# u16_zxbus_rev_a.net
KiCad netlist of a schematic drawn in EAGLE
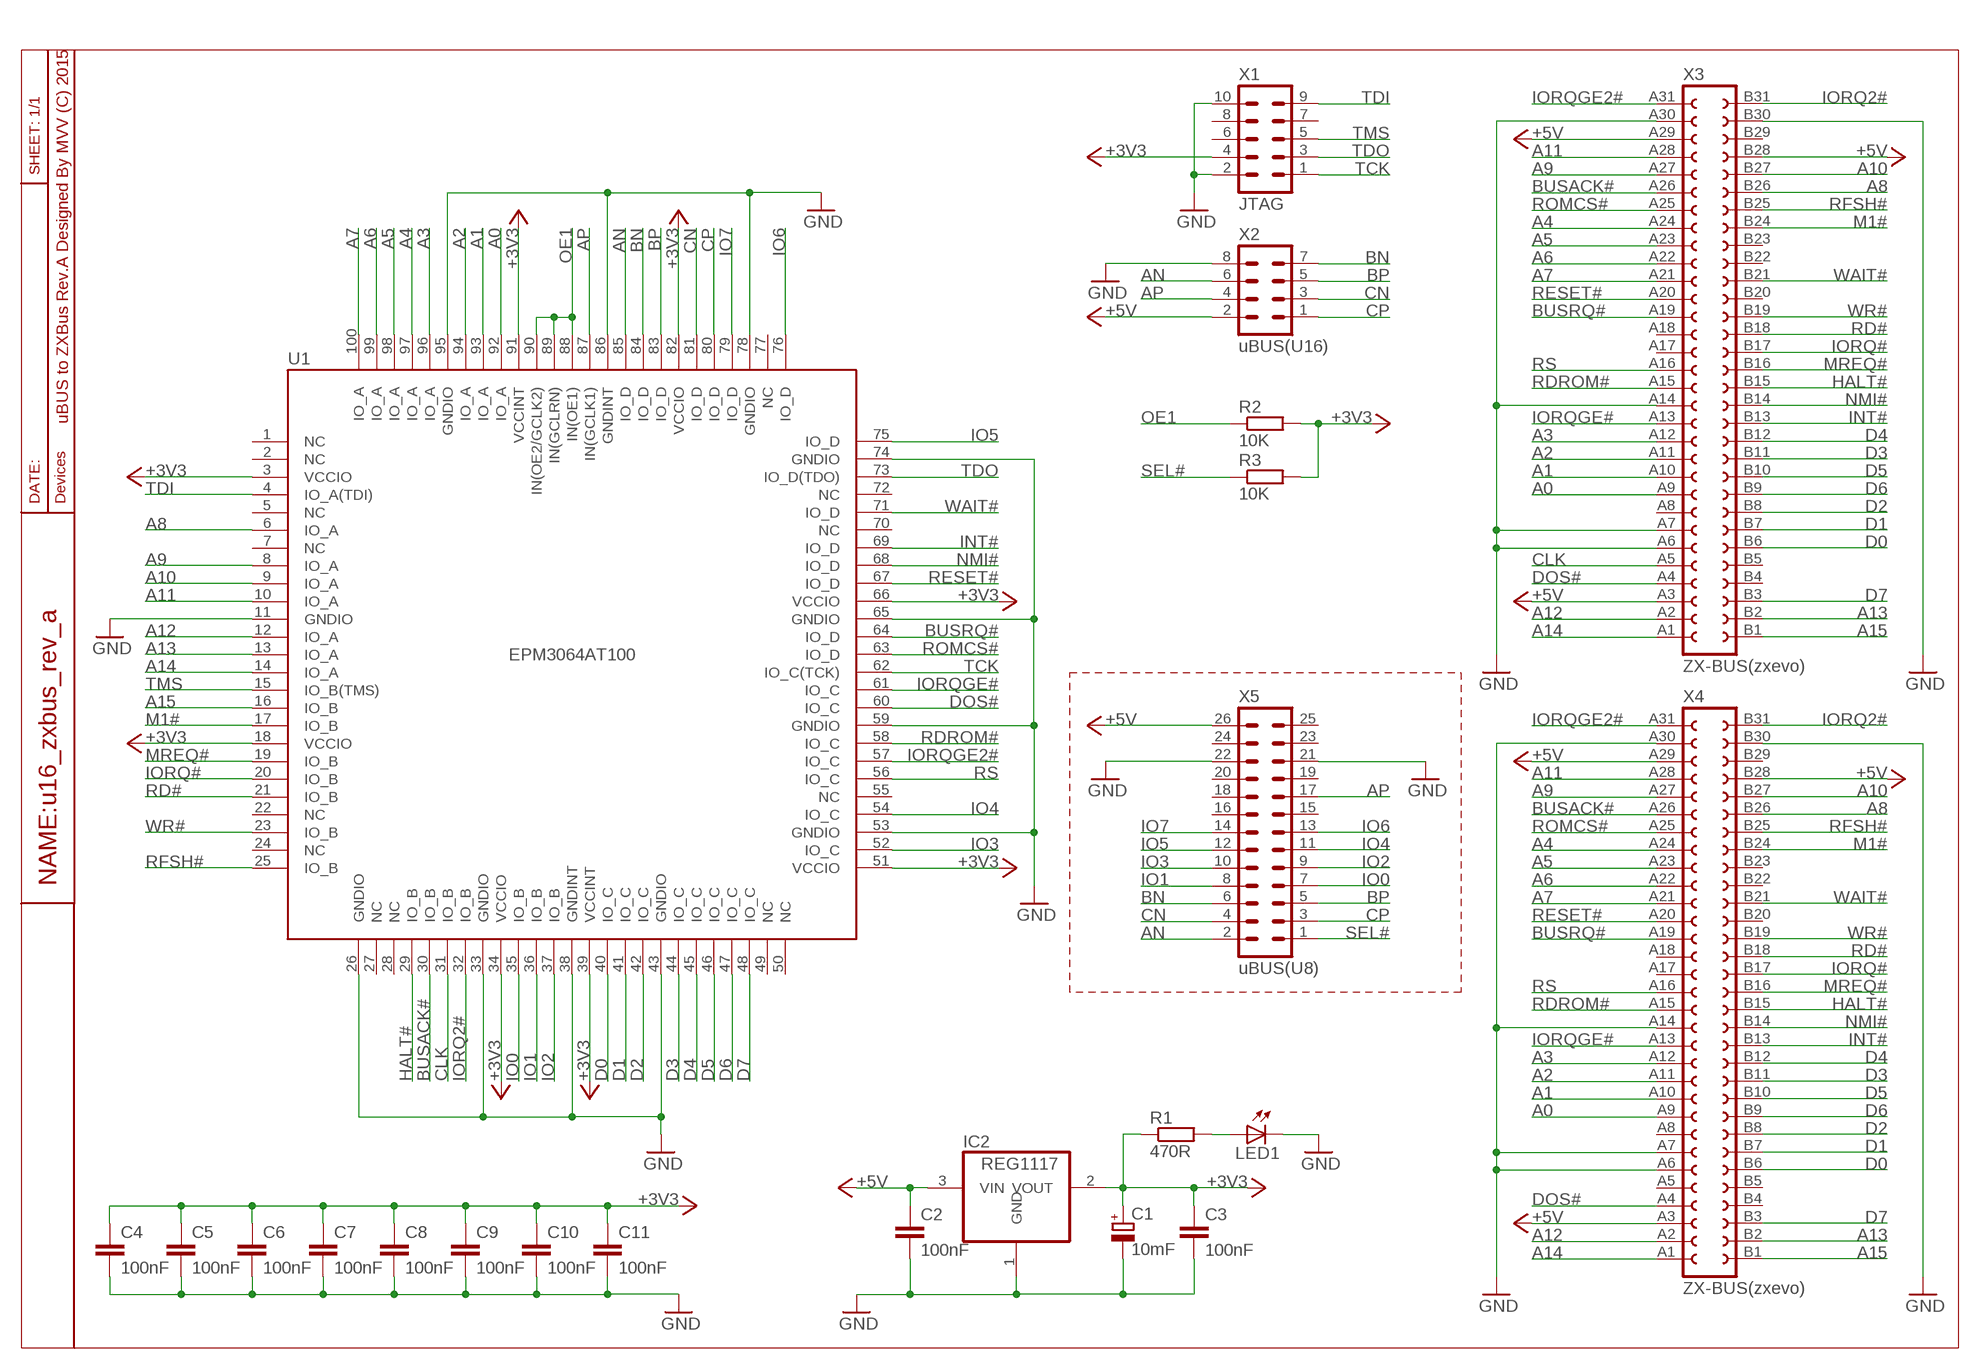
[diagram p0: schematic, sheet 1]

(export (version "E")
  (design (tool "Eeschema 10.0.6"))
  (components
    (comp (ref "C1")
      (value "10mF")
      (footprint "eagle-import:CT6032")
      (libsource (lib "eagle-import") (part "CPOL-EUCT6032"))
    )
    (comp (ref "C2")
      (value "100nF")
      (footprint "eagle-import:C0805")
      (libsource (lib "eagle-import") (part "C-EUC0805"))
    )
    (comp (ref "C3")
      (value "100nF")
      (footprint "eagle-import:C0805")
      (libsource (lib "eagle-import") (part "C-EUC0805"))
    )
    (comp (ref "C4")
      (value "100nF")
      (footprint "eagle-import:C0805")
      (libsource (lib "eagle-import") (part "C-EUC0805"))
    )
    (comp (ref "C5")
      (value "100nF")
      (footprint "eagle-import:C0805")
      (libsource (lib "eagle-import") (part "C-EUC0805"))
    )
    (comp (ref "C6")
      (value "100nF")
      (footprint "eagle-import:C0805")
      (libsource (lib "eagle-import") (part "C-EUC0805"))
    )
    (comp (ref "C7")
      (value "100nF")
      (footprint "eagle-import:C0805")
      (libsource (lib "eagle-import") (part "C-EUC0805"))
    )
    (comp (ref "C8")
      (value "100nF")
      (footprint "eagle-import:C0805")
      (libsource (lib "eagle-import") (part "C-EUC0805"))
    )
    (comp (ref "C9")
      (value "100nF")
      (footprint "eagle-import:C0805")
      (libsource (lib "eagle-import") (part "C-EUC0805"))
    )
    (comp (ref "C10")
      (value "100nF")
      (footprint "eagle-import:C0805")
      (libsource (lib "eagle-import") (part "C-EUC0805"))
    )
    (comp (ref "C11")
      (value "100nF")
      (footprint "eagle-import:C0805")
      (libsource (lib "eagle-import") (part "C-EUC0805"))
    )
    (comp (ref "IC2")
      (value "REG1117")
      (footprint "eagle-import:SOT223")
      (libsource (lib "eagle-import") (part "REG1117"))
    )
    (comp (ref "LED1")
      (value "LEDCHIPLED_0805")
      (footprint "eagle-import:CHIPLED_0805")
      (libsource (lib "eagle-import") (part "LEDCHIPLED_0805"))
    )
    (comp (ref "R1")
      (value "470R")
      (footprint "eagle-import:R0805")
      (libsource (lib "eagle-import") (part "R-EU_R0805"))
    )
    (comp (ref "R2")
      (value "10K")
      (footprint "eagle-import:R0805")
      (libsource (lib "eagle-import") (part "R-EU_R0805"))
    )
    (comp (ref "R3")
      (value "10K")
      (footprint "eagle-import:R0805")
      (libsource (lib "eagle-import") (part "R-EU_R0805"))
    )
    (comp (ref "U1")
      (value "EPM3064AT100")
      (footprint "eagle-import:TQFP100")
      (libsource (lib "eagle-import") (part "EPM3064AT100"))
    )
    (comp (ref "X1")
      (value "JTAG")
      (footprint "eagle-import:ML10")
      (libsource (lib "eagle-import") (part "ML10"))
    )
    (comp (ref "X2")
      (value "uBUS(U16)")
      (footprint "eagle-import:MA04-2")
      (libsource (lib "eagle-import") (part "MA04-2"))
    )
    (comp (ref "X3")
      (value "ZX-BUS(zxevo)")
      (footprint "eagle-import:FE31-2")
      (libsource (lib "eagle-import") (part "FE31-2"))
    )
    (comp (ref "X4")
      (value "ZX-BUS(zxevo)")
      (footprint "eagle-import:ESO3101")
      (libsource (lib "eagle-import") (part "ESO3101"))
    )
    (comp (ref "X5")
      (value "uBUS(U8)")
      (footprint "eagle-import:ML26")
      (libsource (lib "eagle-import") (part "ML26"))
    )
  )
  (nets
    (net (code "1") (name "+3V3") (class "Default")
      (node (ref "C1") (pin "+") (pinfunction "+_+") (pintype "passive"))
      (node (ref "C10") (pin "1") (pinfunction "1_1") (pintype "passive"))
      (node (ref "C11") (pin "1") (pinfunction "1_1") (pintype "passive"))
      (node (ref "C3") (pin "1") (pinfunction "1_1") (pintype "passive"))
      (node (ref "C4") (pin "1") (pinfunction "1_1") (pintype "passive"))
      (node (ref "C5") (pin "1") (pinfunction "1_1") (pintype "passive"))
      (node (ref "C6") (pin "1") (pinfunction "1_1") (pintype "passive"))
      (node (ref "C7") (pin "1") (pinfunction "1_1") (pintype "passive"))
      (node (ref "C8") (pin "1") (pinfunction "1_1") (pintype "passive"))
      (node (ref "C9") (pin "1") (pinfunction "1_1") (pintype "passive"))
      (node (ref "IC2") (pin "2") (pinfunction "VOUT_2") (pintype "output"))
      (node (ref "R1") (pin "1") (pinfunction "1_1") (pintype "passive"))
      (node (ref "R2") (pin "2") (pinfunction "2_2") (pintype "passive"))
      (node (ref "R3") (pin "2") (pinfunction "2_2") (pintype "passive"))
      (node (ref "U1") (pin "18") (pinfunction "VCCIO_18") (pintype "power_in"))
      (node (ref "U1") (pin "3") (pinfunction "VCCIO_3") (pintype "power_in"))
      (node (ref "U1") (pin "34") (pinfunction "VCCIO_34") (pintype "power_in"))
      (node (ref "U1") (pin "39") (pinfunction "VCCINT_39") (pintype "power_in"))
      (node (ref "U1") (pin "51") (pinfunction "VCCIO_51") (pintype "power_in"))
      (node (ref "U1") (pin "66") (pinfunction "VCCIO_66") (pintype "power_in"))
      (node (ref "U1") (pin "82") (pinfunction "VCCIO_82") (pintype "power_in"))
      (node (ref "U1") (pin "91") (pinfunction "VCCINT_91") (pintype "power_in"))
      (node (ref "X1") (pin "4") (pinfunction "4_4") (pintype "passive"))
    )
    (net (code "2") (name "+5V") (class "Default")
      (node (ref "C2") (pin "1") (pinfunction "1_1") (pintype "passive"))
      (node (ref "IC2") (pin "3") (pinfunction "VIN_3") (pintype "input"))
      (node (ref "X2") (pin "2") (pinfunction "2_2") (pintype "passive"))
      (node (ref "X3") (pin "A29") (pinfunction "A29_A29") (pintype "passive"))
      (node (ref "X3") (pin "A3") (pinfunction "A3_A3") (pintype "passive"))
      (node (ref "X3") (pin "B28") (pinfunction "B28_B28") (pintype "passive"))
      (node (ref "X4") (pin "A29") (pinfunction "A29_A29") (pintype "passive"))
      (node (ref "X4") (pin "A3") (pinfunction "A3_A3") (pintype "passive"))
      (node (ref "X4") (pin "B28") (pinfunction "B28_B28") (pintype "passive"))
      (node (ref "X5") (pin "26") (pinfunction "26_26") (pintype "passive"))
    )
    (net (code "3") (name "/A0") (class "Default")
      (node (ref "U1") (pin "92") (pinfunction "IO_A_92") (pintype "bidirectional"))
      (node (ref "X3") (pin "A9") (pinfunction "A9_A9") (pintype "passive"))
      (node (ref "X4") (pin "A9") (pinfunction "A9_A9") (pintype "passive"))
    )
    (net (code "4") (name "/A1") (class "Default")
      (node (ref "U1") (pin "93") (pinfunction "IO_A_93") (pintype "bidirectional"))
      (node (ref "X3") (pin "A10") (pinfunction "A10_A10") (pintype "passive"))
      (node (ref "X4") (pin "A10") (pinfunction "A10_A10") (pintype "passive"))
    )
    (net (code "5") (name "/A2") (class "Default")
      (node (ref "U1") (pin "94") (pinfunction "IO_A_94") (pintype "bidirectional"))
      (node (ref "X3") (pin "A11") (pinfunction "A11_A11") (pintype "passive"))
      (node (ref "X4") (pin "A11") (pinfunction "A11_A11") (pintype "passive"))
    )
    (net (code "6") (name "/A3") (class "Default")
      (node (ref "U1") (pin "96") (pinfunction "IO_A_96") (pintype "bidirectional"))
      (node (ref "X3") (pin "A12") (pinfunction "A12_A12") (pintype "passive"))
      (node (ref "X4") (pin "A12") (pinfunction "A12_A12") (pintype "passive"))
    )
    (net (code "7") (name "/A4") (class "Default")
      (node (ref "U1") (pin "97") (pinfunction "IO_A_97") (pintype "bidirectional"))
      (node (ref "X3") (pin "A24") (pinfunction "A24_A24") (pintype "passive"))
      (node (ref "X4") (pin "A24") (pinfunction "A24_A24") (pintype "passive"))
    )
    (net (code "8") (name "/A5") (class "Default")
      (node (ref "U1") (pin "98") (pinfunction "IO_A_98") (pintype "bidirectional"))
      (node (ref "X3") (pin "A23") (pinfunction "A23_A23") (pintype "passive"))
      (node (ref "X4") (pin "A23") (pinfunction "A23_A23") (pintype "passive"))
    )
    (net (code "9") (name "/A6") (class "Default")
      (node (ref "U1") (pin "99") (pinfunction "IO_A_99") (pintype "bidirectional"))
      (node (ref "X3") (pin "A22") (pinfunction "A22_A22") (pintype "passive"))
      (node (ref "X4") (pin "A22") (pinfunction "A22_A22") (pintype "passive"))
    )
    (net (code "10") (name "/A7") (class "Default")
      (node (ref "U1") (pin "100") (pinfunction "IO_A_100") (pintype "bidirectional"))
      (node (ref "X3") (pin "A21") (pinfunction "A21_A21") (pintype "passive"))
      (node (ref "X4") (pin "A21") (pinfunction "A21_A21") (pintype "passive"))
    )
    (net (code "11") (name "/A8") (class "Default")
      (node (ref "U1") (pin "6") (pinfunction "IO_A_6") (pintype "bidirectional"))
      (node (ref "X3") (pin "B26") (pinfunction "B26_B26") (pintype "passive"))
      (node (ref "X4") (pin "B26") (pinfunction "B26_B26") (pintype "passive"))
    )
    (net (code "12") (name "/A9") (class "Default")
      (node (ref "U1") (pin "8") (pinfunction "IO_A_8") (pintype "bidirectional"))
      (node (ref "X3") (pin "A27") (pinfunction "A27_A27") (pintype "passive"))
      (node (ref "X4") (pin "A27") (pinfunction "A27_A27") (pintype "passive"))
    )
    (net (code "13") (name "/A10") (class "Default")
      (node (ref "U1") (pin "9") (pinfunction "IO_A_9") (pintype "bidirectional"))
      (node (ref "X3") (pin "B27") (pinfunction "B27_B27") (pintype "passive"))
      (node (ref "X4") (pin "B27") (pinfunction "B27_B27") (pintype "passive"))
    )
    (net (code "14") (name "/A11") (class "Default")
      (node (ref "U1") (pin "10") (pinfunction "IO_A_10") (pintype "bidirectional"))
      (node (ref "X3") (pin "A28") (pinfunction "A28_A28") (pintype "passive"))
      (node (ref "X4") (pin "A28") (pinfunction "A28_A28") (pintype "passive"))
    )
    (net (code "15") (name "/A12") (class "Default")
      (node (ref "U1") (pin "12") (pinfunction "IO_A_12") (pintype "bidirectional"))
      (node (ref "X3") (pin "A2") (pinfunction "A2_A2") (pintype "passive"))
      (node (ref "X4") (pin "A2") (pinfunction "A2_A2") (pintype "passive"))
    )
    (net (code "16") (name "/A13") (class "Default")
      (node (ref "U1") (pin "13") (pinfunction "IO_A_13") (pintype "bidirectional"))
      (node (ref "X3") (pin "B2") (pinfunction "B2_B2") (pintype "passive"))
      (node (ref "X4") (pin "B2") (pinfunction "B2_B2") (pintype "passive"))
    )
    (net (code "17") (name "/A14") (class "Default")
      (node (ref "U1") (pin "14") (pinfunction "IO_A_14") (pintype "bidirectional"))
      (node (ref "X3") (pin "A1") (pinfunction "A1_A1") (pintype "passive"))
      (node (ref "X4") (pin "A1") (pinfunction "A1_A1") (pintype "passive"))
    )
    (net (code "18") (name "/A15") (class "Default")
      (node (ref "U1") (pin "16") (pinfunction "IO_B_16") (pintype "bidirectional"))
      (node (ref "X3") (pin "B1") (pinfunction "B1_B1") (pintype "passive"))
      (node (ref "X4") (pin "B1") (pinfunction "B1_B1") (pintype "passive"))
    )
    (net (code "19") (name "/AN") (class "Default")
      (node (ref "U1") (pin "85") (pinfunction "IO_D_85") (pintype "bidirectional"))
      (node (ref "X2") (pin "6") (pinfunction "6_6") (pintype "passive"))
      (node (ref "X5") (pin "2") (pinfunction "2_2") (pintype "passive"))
    )
    (net (code "20") (name "/AP") (class "Default")
      (node (ref "U1") (pin "87") (pinfunction "IN(GCLK1)_87") (pintype "input"))
      (node (ref "X2") (pin "4") (pinfunction "4_4") (pintype "passive"))
      (node (ref "X5") (pin "17") (pinfunction "17_17") (pintype "passive"))
    )
    (net (code "21") (name "/BN") (class "Default")
      (node (ref "U1") (pin "84") (pinfunction "IO_D_84") (pintype "bidirectional"))
      (node (ref "X2") (pin "7") (pinfunction "7_7") (pintype "passive"))
      (node (ref "X5") (pin "6") (pinfunction "6_6") (pintype "passive"))
    )
    (net (code "22") (name "/BP") (class "Default")
      (node (ref "U1") (pin "83") (pinfunction "IO_D_83") (pintype "bidirectional"))
      (node (ref "X2") (pin "5") (pinfunction "5_5") (pintype "passive"))
      (node (ref "X5") (pin "5") (pinfunction "5_5") (pintype "passive"))
    )
    (net (code "23") (name "/BUSACK#") (class "Default")
      (node (ref "U1") (pin "30") (pinfunction "IO_B_30") (pintype "bidirectional"))
      (node (ref "X3") (pin "A26") (pinfunction "A26_A26") (pintype "passive"))
      (node (ref "X4") (pin "A26") (pinfunction "A26_A26") (pintype "passive"))
    )
    (net (code "24") (name "/BUSRQ#") (class "Default")
      (node (ref "U1") (pin "64") (pinfunction "IO_D_64") (pintype "bidirectional"))
      (node (ref "X3") (pin "A19") (pinfunction "A19_A19") (pintype "passive"))
      (node (ref "X4") (pin "A19") (pinfunction "A19_A19") (pintype "passive"))
    )
    (net (code "25") (name "/CLK") (class "Default")
      (node (ref "U1") (pin "31") (pinfunction "IO_B_31") (pintype "bidirectional"))
      (node (ref "X3") (pin "A5") (pinfunction "A5_A5") (pintype "passive"))
    )
    (net (code "26") (name "/CN") (class "Default")
      (node (ref "U1") (pin "81") (pinfunction "IO_D_81") (pintype "bidirectional"))
      (node (ref "X2") (pin "3") (pinfunction "3_3") (pintype "passive"))
      (node (ref "X5") (pin "4") (pinfunction "4_4") (pintype "passive"))
    )
    (net (code "27") (name "/CP") (class "Default")
      (node (ref "U1") (pin "80") (pinfunction "IO_D_80") (pintype "bidirectional"))
      (node (ref "X2") (pin "1") (pinfunction "1_1") (pintype "passive"))
      (node (ref "X5") (pin "3") (pinfunction "3_3") (pintype "passive"))
    )
    (net (code "28") (name "/D0") (class "Default")
      (node (ref "U1") (pin "40") (pinfunction "IO_C_40") (pintype "bidirectional"))
      (node (ref "X3") (pin "B6") (pinfunction "B6_B6") (pintype "passive"))
      (node (ref "X4") (pin "B6") (pinfunction "B6_B6") (pintype "passive"))
    )
    (net (code "29") (name "/D1") (class "Default")
      (node (ref "U1") (pin "41") (pinfunction "IO_C_41") (pintype "bidirectional"))
      (node (ref "X3") (pin "B7") (pinfunction "B7_B7") (pintype "passive"))
      (node (ref "X4") (pin "B7") (pinfunction "B7_B7") (pintype "passive"))
    )
    (net (code "30") (name "/D2") (class "Default")
      (node (ref "U1") (pin "42") (pinfunction "IO_C_42") (pintype "bidirectional"))
      (node (ref "X3") (pin "B8") (pinfunction "B8_B8") (pintype "passive"))
      (node (ref "X4") (pin "B8") (pinfunction "B8_B8") (pintype "passive"))
    )
    (net (code "31") (name "/D3") (class "Default")
      (node (ref "U1") (pin "44") (pinfunction "IO_C_44") (pintype "bidirectional"))
      (node (ref "X3") (pin "B11") (pinfunction "B11_B11") (pintype "passive"))
      (node (ref "X4") (pin "B11") (pinfunction "B11_B11") (pintype "passive"))
    )
    (net (code "32") (name "/D4") (class "Default")
      (node (ref "U1") (pin "45") (pinfunction "IO_C_45") (pintype "bidirectional"))
      (node (ref "X3") (pin "B12") (pinfunction "B12_B12") (pintype "passive"))
      (node (ref "X4") (pin "B12") (pinfunction "B12_B12") (pintype "passive"))
    )
    (net (code "33") (name "/D5") (class "Default")
      (node (ref "U1") (pin "46") (pinfunction "IO_C_46") (pintype "bidirectional"))
      (node (ref "X3") (pin "B10") (pinfunction "B10_B10") (pintype "passive"))
      (node (ref "X4") (pin "B10") (pinfunction "B10_B10") (pintype "passive"))
    )
    (net (code "34") (name "/D6") (class "Default")
      (node (ref "U1") (pin "47") (pinfunction "IO_C_47") (pintype "bidirectional"))
      (node (ref "X3") (pin "B9") (pinfunction "B9_B9") (pintype "passive"))
      (node (ref "X4") (pin "B9") (pinfunction "B9_B9") (pintype "passive"))
    )
    (net (code "35") (name "/D7") (class "Default")
      (node (ref "U1") (pin "48") (pinfunction "IO_C_48") (pintype "bidirectional"))
      (node (ref "X3") (pin "B3") (pinfunction "B3_B3") (pintype "passive"))
      (node (ref "X4") (pin "B3") (pinfunction "B3_B3") (pintype "passive"))
    )
    (net (code "36") (name "/DOS#") (class "Default")
      (node (ref "U1") (pin "60") (pinfunction "IO_C_60") (pintype "bidirectional"))
      (node (ref "X3") (pin "A4") (pinfunction "A4_A4") (pintype "passive"))
      (node (ref "X4") (pin "A4") (pinfunction "A4_A4") (pintype "passive"))
    )
    (net (code "37") (name "/HALT#") (class "Default")
      (node (ref "U1") (pin "29") (pinfunction "IO_B_29") (pintype "bidirectional"))
      (node (ref "X3") (pin "B15") (pinfunction "B15_B15") (pintype "passive"))
      (node (ref "X4") (pin "B15") (pinfunction "B15_B15") (pintype "passive"))
    )
    (net (code "38") (name "/INT#") (class "Default")
      (node (ref "U1") (pin "69") (pinfunction "IO_D_69") (pintype "bidirectional"))
      (node (ref "X3") (pin "B13") (pinfunction "B13_B13") (pintype "passive"))
      (node (ref "X4") (pin "B13") (pinfunction "B13_B13") (pintype "passive"))
    )
    (net (code "39") (name "/IO0") (class "Default")
      (node (ref "U1") (pin "35") (pinfunction "IO_B_35") (pintype "bidirectional"))
      (node (ref "X5") (pin "7") (pinfunction "7_7") (pintype "passive"))
    )
    (net (code "40") (name "/IO1") (class "Default")
      (node (ref "U1") (pin "36") (pinfunction "IO_B_36") (pintype "bidirectional"))
      (node (ref "X5") (pin "8") (pinfunction "8_8") (pintype "passive"))
    )
    (net (code "41") (name "/IO2") (class "Default")
      (node (ref "U1") (pin "37") (pinfunction "IO_B_37") (pintype "bidirectional"))
      (node (ref "X5") (pin "9") (pinfunction "9_9") (pintype "passive"))
    )
    (net (code "42") (name "/IO3") (class "Default")
      (node (ref "U1") (pin "52") (pinfunction "IO_C_52") (pintype "bidirectional"))
      (node (ref "X5") (pin "10") (pinfunction "10_10") (pintype "passive"))
    )
    (net (code "43") (name "/IO4") (class "Default")
      (node (ref "U1") (pin "54") (pinfunction "IO_C_54") (pintype "bidirectional"))
      (node (ref "X5") (pin "11") (pinfunction "11_11") (pintype "passive"))
    )
    (net (code "44") (name "/IO5") (class "Default")
      (node (ref "U1") (pin "75") (pinfunction "IO_D_75") (pintype "bidirectional"))
      (node (ref "X5") (pin "12") (pinfunction "12_12") (pintype "passive"))
    )
    (net (code "45") (name "/IO6") (class "Default")
      (node (ref "U1") (pin "76") (pinfunction "IO_D_76") (pintype "bidirectional"))
      (node (ref "X5") (pin "13") (pinfunction "13_13") (pintype "passive"))
    )
    (net (code "46") (name "/IO7") (class "Default")
      (node (ref "U1") (pin "79") (pinfunction "IO_D_79") (pintype "bidirectional"))
      (node (ref "X5") (pin "14") (pinfunction "14_14") (pintype "passive"))
    )
    (net (code "47") (name "/IORQ#") (class "Default")
      (node (ref "U1") (pin "20") (pinfunction "IO_B_20") (pintype "bidirectional"))
      (node (ref "X3") (pin "B17") (pinfunction "B17_B17") (pintype "passive"))
      (node (ref "X4") (pin "B17") (pinfunction "B17_B17") (pintype "passive"))
    )
    (net (code "48") (name "/IORQ2#") (class "Default")
      (node (ref "U1") (pin "32") (pinfunction "IO_B_32") (pintype "bidirectional"))
      (node (ref "X3") (pin "B31") (pinfunction "B31_B31") (pintype "passive"))
      (node (ref "X4") (pin "B31") (pinfunction "B31_B31") (pintype "passive"))
    )
    (net (code "49") (name "/IORQGE#") (class "Default")
      (node (ref "U1") (pin "61") (pinfunction "IO_C_61") (pintype "bidirectional"))
      (node (ref "X3") (pin "A13") (pinfunction "A13_A13") (pintype "passive"))
      (node (ref "X4") (pin "A13") (pinfunction "A13_A13") (pintype "passive"))
    )
    (net (code "50") (name "/IORQGE2#") (class "Default")
      (node (ref "U1") (pin "57") (pinfunction "IO_C_57") (pintype "bidirectional"))
      (node (ref "X3") (pin "A31") (pinfunction "A31_A31") (pintype "passive"))
      (node (ref "X4") (pin "A31") (pinfunction "A31_A31") (pintype "passive"))
    )
    (net (code "51") (name "/M1#") (class "Default")
      (node (ref "U1") (pin "17") (pinfunction "IO_B_17") (pintype "bidirectional"))
      (node (ref "X3") (pin "B24") (pinfunction "B24_B24") (pintype "passive"))
      (node (ref "X4") (pin "B24") (pinfunction "B24_B24") (pintype "passive"))
    )
    (net (code "52") (name "/MREQ#") (class "Default")
      (node (ref "U1") (pin "19") (pinfunction "IO_B_19") (pintype "bidirectional"))
      (node (ref "X3") (pin "B16") (pinfunction "B16_B16") (pintype "passive"))
      (node (ref "X4") (pin "B16") (pinfunction "B16_B16") (pintype "passive"))
    )
    (net (code "53") (name "/NMI#") (class "Default")
      (node (ref "U1") (pin "68") (pinfunction "IO_D_68") (pintype "bidirectional"))
      (node (ref "X3") (pin "B14") (pinfunction "B14_B14") (pintype "passive"))
      (node (ref "X4") (pin "B14") (pinfunction "B14_B14") (pintype "passive"))
    )
    (net (code "54") (name "/OE1") (class "Default")
      (node (ref "R2") (pin "1") (pinfunction "1_1") (pintype "passive"))
      (node (ref "U1") (pin "88") (pinfunction "IN(OE1)_88") (pintype "input"))
      (node (ref "U1") (pin "89") (pinfunction "IN(GCLRN)_89") (pintype "input"))
      (node (ref "U1") (pin "90") (pinfunction "IN(OE2/GCLK2)_90") (pintype "input"))
    )
    (net (code "55") (name "/RD#") (class "Default")
      (node (ref "U1") (pin "21") (pinfunction "IO_B_21") (pintype "bidirectional"))
      (node (ref "X3") (pin "B18") (pinfunction "B18_B18") (pintype "passive"))
      (node (ref "X4") (pin "B18") (pinfunction "B18_B18") (pintype "passive"))
    )
    (net (code "56") (name "/RDROM#") (class "Default")
      (node (ref "U1") (pin "58") (pinfunction "IO_C_58") (pintype "bidirectional"))
      (node (ref "X3") (pin "A15") (pinfunction "A15_A15") (pintype "passive"))
      (node (ref "X4") (pin "A15") (pinfunction "A15_A15") (pintype "passive"))
    )
    (net (code "57") (name "/RESET#") (class "Default")
      (node (ref "U1") (pin "67") (pinfunction "IO_D_67") (pintype "bidirectional"))
      (node (ref "X3") (pin "A20") (pinfunction "A20_A20") (pintype "passive"))
      (node (ref "X4") (pin "A20") (pinfunction "A20_A20") (pintype "passive"))
    )
    (net (code "58") (name "/RFSH#") (class "Default")
      (node (ref "U1") (pin "25") (pinfunction "IO_B_25") (pintype "bidirectional"))
      (node (ref "X3") (pin "B25") (pinfunction "B25_B25") (pintype "passive"))
      (node (ref "X4") (pin "B25") (pinfunction "B25_B25") (pintype "passive"))
    )
    (net (code "59") (name "/ROMCS#") (class "Default")
      (node (ref "U1") (pin "63") (pinfunction "IO_D_63") (pintype "bidirectional"))
      (node (ref "X3") (pin "A25") (pinfunction "A25_A25") (pintype "passive"))
      (node (ref "X4") (pin "A25") (pinfunction "A25_A25") (pintype "passive"))
    )
    (net (code "60") (name "/RS") (class "Default")
      (node (ref "U1") (pin "56") (pinfunction "IO_C_56") (pintype "bidirectional"))
      (node (ref "X3") (pin "A16") (pinfunction "A16_A16") (pintype "passive"))
      (node (ref "X4") (pin "A16") (pinfunction "A16_A16") (pintype "passive"))
    )
    (net (code "61") (name "/SEL#") (class "Default")
      (node (ref "R3") (pin "1") (pinfunction "1_1") (pintype "passive"))
      (node (ref "X5") (pin "1") (pinfunction "1_1") (pintype "passive"))
    )
    (net (code "62") (name "/TCK") (class "Default")
      (node (ref "U1") (pin "62") (pinfunction "IO_C(TCK)_62") (pintype "bidirectional"))
      (node (ref "X1") (pin "1") (pinfunction "1_1") (pintype "passive"))
    )
    (net (code "63") (name "/TDI") (class "Default")
      (node (ref "U1") (pin "4") (pinfunction "IO_A(TDI)_4") (pintype "bidirectional"))
      (node (ref "X1") (pin "9") (pinfunction "9_9") (pintype "passive"))
    )
    (net (code "64") (name "/TDO") (class "Default")
      (node (ref "U1") (pin "73") (pinfunction "IO_D(TDO)_73") (pintype "bidirectional"))
      (node (ref "X1") (pin "3") (pinfunction "3_3") (pintype "passive"))
    )
    (net (code "65") (name "/TMS") (class "Default")
      (node (ref "U1") (pin "15") (pinfunction "IO_B(TMS)_15") (pintype "bidirectional"))
      (node (ref "X1") (pin "5") (pinfunction "5_5") (pintype "passive"))
    )
    (net (code "66") (name "/WAIT#") (class "Default")
      (node (ref "U1") (pin "71") (pinfunction "IO_D_71") (pintype "bidirectional"))
      (node (ref "X3") (pin "B21") (pinfunction "B21_B21") (pintype "passive"))
      (node (ref "X4") (pin "B21") (pinfunction "B21_B21") (pintype "passive"))
    )
    (net (code "67") (name "/WR#") (class "Default")
      (node (ref "U1") (pin "23") (pinfunction "IO_B_23") (pintype "bidirectional"))
      (node (ref "X3") (pin "B19") (pinfunction "B19_B19") (pintype "passive"))
      (node (ref "X4") (pin "B19") (pinfunction "B19_B19") (pintype "passive"))
    )
    (net (code "68") (name "GND") (class "Default")
      (node (ref "C1") (pin "-") (pinfunction "-_-") (pintype "passive"))
      (node (ref "C10") (pin "2") (pinfunction "2_2") (pintype "passive"))
      (node (ref "C11") (pin "2") (pinfunction "2_2") (pintype "passive"))
      (node (ref "C2") (pin "2") (pinfunction "2_2") (pintype "passive"))
      (node (ref "C3") (pin "2") (pinfunction "2_2") (pintype "passive"))
      (node (ref "C4") (pin "2") (pinfunction "2_2") (pintype "passive"))
      (node (ref "C5") (pin "2") (pinfunction "2_2") (pintype "passive"))
      (node (ref "C6") (pin "2") (pinfunction "2_2") (pintype "passive"))
      (node (ref "C7") (pin "2") (pinfunction "2_2") (pintype "passive"))
      (node (ref "C8") (pin "2") (pinfunction "2_2") (pintype "passive"))
      (node (ref "C9") (pin "2") (pinfunction "2_2") (pintype "passive"))
      (node (ref "IC2") (pin "1") (pinfunction "GND_1") (pintype "power_in"))
      (node (ref "LED1") (pin "C") (pinfunction "C_C") (pintype "passive"))
      (node (ref "U1") (pin "11") (pinfunction "GNDIO_11") (pintype "power_in"))
      (node (ref "U1") (pin "26") (pinfunction "GNDIO_26") (pintype "power_in"))
      (node (ref "U1") (pin "33") (pinfunction "GNDIO_33") (pintype "power_in"))
      (node (ref "U1") (pin "38") (pinfunction "GNDINT_38") (pintype "power_in"))
      (node (ref "U1") (pin "43") (pinfunction "GNDIO_43") (pintype "power_in"))
      (node (ref "U1") (pin "53") (pinfunction "GNDIO_53") (pintype "power_in"))
      (node (ref "U1") (pin "59") (pinfunction "GNDIO_59") (pintype "power_in"))
      (node (ref "U1") (pin "65") (pinfunction "GNDIO_65") (pintype "power_in"))
      (node (ref "U1") (pin "74") (pinfunction "GNDIO_74") (pintype "power_in"))
      (node (ref "U1") (pin "78") (pinfunction "GNDIO_78") (pintype "power_in"))
      (node (ref "U1") (pin "86") (pinfunction "GNDINT_86") (pintype "power_in"))
      (node (ref "U1") (pin "95") (pinfunction "GNDIO_95") (pintype "power_in"))
      (node (ref "X1") (pin "10") (pinfunction "10_10") (pintype "passive"))
      (node (ref "X1") (pin "2") (pinfunction "2_2") (pintype "passive"))
      (node (ref "X2") (pin "8") (pinfunction "8_8") (pintype "passive"))
      (node (ref "X3") (pin "A14") (pinfunction "A14_A14") (pintype "passive"))
      (node (ref "X3") (pin "A30") (pinfunction "A30_A30") (pintype "passive"))
      (node (ref "X3") (pin "A6") (pinfunction "A6_A6") (pintype "passive"))
      (node (ref "X3") (pin "A7") (pinfunction "A7_A7") (pintype "passive"))
      (node (ref "X3") (pin "B30") (pinfunction "B30_B30") (pintype "passive"))
      (node (ref "X4") (pin "A14") (pinfunction "A14_A14") (pintype "passive"))
      (node (ref "X4") (pin "A30") (pinfunction "A30_A30") (pintype "passive"))
      (node (ref "X4") (pin "A6") (pinfunction "A6_A6") (pintype "passive"))
      (node (ref "X4") (pin "A7") (pinfunction "A7_A7") (pintype "passive"))
      (node (ref "X4") (pin "B30") (pinfunction "B30_B30") (pintype "passive"))
      (node (ref "X5") (pin "21") (pinfunction "21_21") (pintype "passive"))
      (node (ref "X5") (pin "22") (pinfunction "22_22") (pintype "passive"))
    )
    (net (code "69") (name "Net-(LED1-PadA)") (class "Default")
      (node (ref "LED1") (pin "A") (pinfunction "A_A") (pintype "passive"))
      (node (ref "R1") (pin "2") (pinfunction "2_2") (pintype "passive"))
    )
    (net (code "70") (name "unconnected-(U1-NC-Pad1)") (class "Default")
      (node (ref "U1") (pin "1") (pinfunction "NC_1") (pintype "passive"))
    )
    (net (code "71") (name "unconnected-(U1-NC-Pad2)") (class "Default")
      (node (ref "U1") (pin "2") (pinfunction "NC_2") (pintype "passive"))
    )
    (net (code "72") (name "unconnected-(U1-NC-Pad5)") (class "Default")
      (node (ref "U1") (pin "5") (pinfunction "NC_5") (pintype "passive"))
    )
    (net (code "73") (name "unconnected-(U1-NC-Pad7)") (class "Default")
      (node (ref "U1") (pin "7") (pinfunction "NC_7") (pintype "passive"))
    )
    (net (code "74") (name "unconnected-(U1-NC-Pad22)") (class "Default")
      (node (ref "U1") (pin "22") (pinfunction "NC_22") (pintype "passive"))
    )
    (net (code "75") (name "unconnected-(U1-NC-Pad24)") (class "Default")
      (node (ref "U1") (pin "24") (pinfunction "NC_24") (pintype "passive"))
    )
    (net (code "76") (name "unconnected-(U1-NC-Pad27)") (class "Default")
      (node (ref "U1") (pin "27") (pinfunction "NC_27") (pintype "passive"))
    )
    (net (code "77") (name "unconnected-(U1-NC-Pad28)") (class "Default")
      (node (ref "U1") (pin "28") (pinfunction "NC_28") (pintype "passive"))
    )
    (net (code "78") (name "unconnected-(U1-NC-Pad49)") (class "Default")
      (node (ref "U1") (pin "49") (pinfunction "NC_49") (pintype "passive"))
    )
    (net (code "79") (name "unconnected-(U1-NC-Pad50)") (class "Default")
      (node (ref "U1") (pin "50") (pinfunction "NC_50") (pintype "passive"))
    )
    (net (code "80") (name "unconnected-(U1-NC-Pad55)") (class "Default")
      (node (ref "U1") (pin "55") (pinfunction "NC_55") (pintype "passive"))
    )
    (net (code "81") (name "unconnected-(U1-NC-Pad70)") (class "Default")
      (node (ref "U1") (pin "70") (pinfunction "NC_70") (pintype "passive"))
    )
    (net (code "82") (name "unconnected-(U1-NC-Pad72)") (class "Default")
      (node (ref "U1") (pin "72") (pinfunction "NC_72") (pintype "passive"))
    )
    (net (code "83") (name "unconnected-(U1-NC-Pad77)") (class "Default")
      (node (ref "U1") (pin "77") (pinfunction "NC_77") (pintype "passive"))
    )
    (net (code "84") (name "unconnected-(X1-Pad6)") (class "Default")
      (node (ref "X1") (pin "6") (pinfunction "6_6") (pintype "passive"))
    )
    (net (code "85") (name "unconnected-(X1-Pad7)") (class "Default")
      (node (ref "X1") (pin "7") (pinfunction "7_7") (pintype "passive"))
    )
    (net (code "86") (name "unconnected-(X1-Pad8)") (class "Default")
      (node (ref "X1") (pin "8") (pinfunction "8_8") (pintype "passive"))
    )
    (net (code "87") (name "unconnected-(X3-PadA8)") (class "Default")
      (node (ref "X3") (pin "A8") (pinfunction "A8_A8") (pintype "passive"))
    )
    (net (code "88") (name "unconnected-(X3-PadA17)") (class "Default")
      (node (ref "X3") (pin "A17") (pinfunction "A17_A17") (pintype "passive"))
    )
    (net (code "89") (name "unconnected-(X3-PadA18)") (class "Default")
      (node (ref "X3") (pin "A18") (pinfunction "A18_A18") (pintype "passive"))
    )
    (net (code "90") (name "unconnected-(X3-PadB4)") (class "Default")
      (node (ref "X3") (pin "B4") (pinfunction "B4_B4") (pintype "passive"))
    )
    (net (code "91") (name "unconnected-(X3-PadB5)") (class "Default")
      (node (ref "X3") (pin "B5") (pinfunction "B5_B5") (pintype "passive"))
    )
    (net (code "92") (name "unconnected-(X3-PadB20)") (class "Default")
      (node (ref "X3") (pin "B20") (pinfunction "B20_B20") (pintype "passive"))
    )
    (net (code "93") (name "unconnected-(X3-PadB22)") (class "Default")
      (node (ref "X3") (pin "B22") (pinfunction "B22_B22") (pintype "passive"))
    )
    (net (code "94") (name "unconnected-(X3-PadB23)") (class "Default")
      (node (ref "X3") (pin "B23") (pinfunction "B23_B23") (pintype "passive"))
    )
    (net (code "95") (name "unconnected-(X3-PadB29)") (class "Default")
      (node (ref "X3") (pin "B29") (pinfunction "B29_B29") (pintype "passive"))
    )
    (net (code "96") (name "unconnected-(X4-PadA5)") (class "Default")
      (node (ref "X4") (pin "A5") (pinfunction "A5_A5") (pintype "passive"))
    )
    (net (code "97") (name "unconnected-(X4-PadA8)") (class "Default")
      (node (ref "X4") (pin "A8") (pinfunction "A8_A8") (pintype "passive"))
    )
    (net (code "98") (name "unconnected-(X4-PadA17)") (class "Default")
      (node (ref "X4") (pin "A17") (pinfunction "A17_A17") (pintype "passive"))
    )
    (net (code "99") (name "unconnected-(X4-PadA18)") (class "Default")
      (node (ref "X4") (pin "A18") (pinfunction "A18_A18") (pintype "passive"))
    )
    (net (code "100") (name "unconnected-(X4-PadB4)") (class "Default")
      (node (ref "X4") (pin "B4") (pinfunction "B4_B4") (pintype "passive"))
    )
    (net (code "101") (name "unconnected-(X4-PadB5)") (class "Default")
      (node (ref "X4") (pin "B5") (pinfunction "B5_B5") (pintype "passive"))
    )
    (net (code "102") (name "unconnected-(X4-PadB20)") (class "Default")
      (node (ref "X4") (pin "B20") (pinfunction "B20_B20") (pintype "passive"))
    )
    (net (code "103") (name "unconnected-(X4-PadB22)") (class "Default")
      (node (ref "X4") (pin "B22") (pinfunction "B22_B22") (pintype "passive"))
    )
    (net (code "104") (name "unconnected-(X4-PadB23)") (class "Default")
      (node (ref "X4") (pin "B23") (pinfunction "B23_B23") (pintype "passive"))
    )
    (net (code "105") (name "unconnected-(X4-PadB29)") (class "Default")
      (node (ref "X4") (pin "B29") (pinfunction "B29_B29") (pintype "passive"))
    )
    (net (code "106") (name "unconnected-(X5-Pad15)") (class "Default")
      (node (ref "X5") (pin "15") (pinfunction "15_15") (pintype "passive"))
    )
    (net (code "107") (name "unconnected-(X5-Pad16)") (class "Default")
      (node (ref "X5") (pin "16") (pinfunction "16_16") (pintype "passive"))
    )
    (net (code "108") (name "unconnected-(X5-Pad18)") (class "Default")
      (node (ref "X5") (pin "18") (pinfunction "18_18") (pintype "passive"))
    )
    (net (code "109") (name "unconnected-(X5-Pad19)") (class "Default")
      (node (ref "X5") (pin "19") (pinfunction "19_19") (pintype "passive"))
    )
    (net (code "110") (name "unconnected-(X5-Pad20)") (class "Default")
      (node (ref "X5") (pin "20") (pinfunction "20_20") (pintype "passive"))
    )
    (net (code "111") (name "unconnected-(X5-Pad23)") (class "Default")
      (node (ref "X5") (pin "23") (pinfunction "23_23") (pintype "passive"))
    )
    (net (code "112") (name "unconnected-(X5-Pad24)") (class "Default")
      (node (ref "X5") (pin "24") (pinfunction "24_24") (pintype "passive"))
    )
    (net (code "113") (name "unconnected-(X5-Pad25)") (class "Default")
      (node (ref "X5") (pin "25") (pinfunction "25_25") (pintype "passive"))
    )
  )
)
